# Power_-_Input.net
KiCad netlist of a schematic drawn in Altium Designer
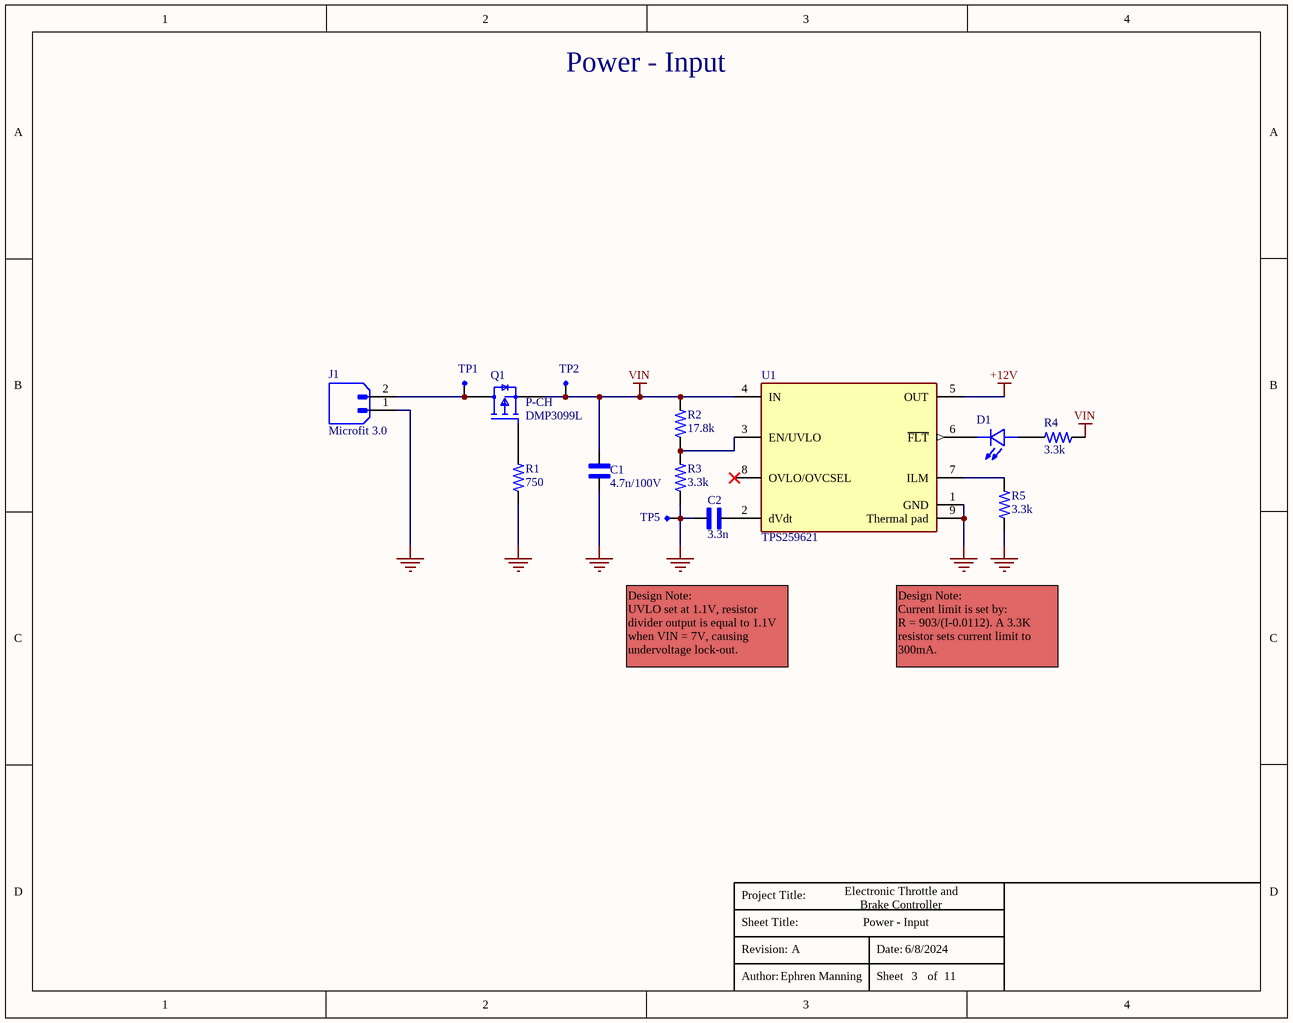
[diagram p0: Power - Input.SchDoc]

(export (version "E")
  (design (tool "Eeschema 10.0.6"))
  (components
    (comp (ref "C1")
      (value "4.7n/100V")
      (footprint "CAP_0402-Footprint-1")
      (description "4.7nF 100V 10% 0402 Ceramic Capacitor")
      (fields (field (name "DIGIKEY PART NUMBER") "490-4765-1-ND"))
      (libsource (lib "SAE @ UIC Formula Electric") (part "CAP_0402-Symbol-1"))
    )
    (comp (ref "C2")
      (value "3.3n")
      (footprint "CAP_0402-Footprint-1")
      (description "3.3nF 25V 0402 Ceramic Capacitor")
      (fields (field (name "DIGIKEY PART NUMBER") "311-3623-1-ND"))
      (libsource (lib "") (part "CAP_0402-Symbol-1_1"))
    )
    (comp (ref "D1")
      (value "150060RS75000")
      (footprint "LED_150060RS75000")
      (description "CLEAR RED LEAD 0603 2V Forward Voltage")
      (fields (field (name "DIGIKEY PART NUMBER") "732-4978-1-ND"))
      (libsource (lib "SAE @ UIC Formula Electric") (part "150060RS75000"))
    )
    (comp (ref "J1")
      (value "Microfit 3.0")
      (footprint "MOLEX_436500216")
      (description "1x2 Gold Microfit")
      (fields (field (name "DIGIKEY PART NUMBER") "WM1922-ND"))
      (libsource (lib "SAE @ UIC Formula Electric") (part "436500216"))
    )
    (comp (ref "Q1")
      (value "DMP3099L")
      (footprint "SOT95P242X110-3N")
      (description "Mosfet P-CH 30V 3.8A Vgs(ON) = -10V SOT23")
      (fields (field (name "DIGIKEY PART NUMBER") "DMP3099L-7DICT-ND"))
      (libsource (lib "SAE @ UIC Formula Electric") (part "DMP3099L-7-Symbol-1"))
    )
    (comp (ref "R1")
      (value "750")
      (footprint "RES_0402-Footprint-1")
      (description "750 1% 1/16W 0402 Thick Film")
      (fields (field (name "DIGIKEY PART NUMBER") "311-750LRCT-ND"))
      (libsource (lib "SAE @ UIC Formula Electric") (part "RES_0402_Symbol"))
    )
    (comp (ref "R2")
      (value "17.8k")
      (footprint "RES_0402-Footprint-1")
      (description "17.8k 1% 1/16W 0402 Thick Film")
      (fields (field (name "DIGIKEY PART NUMBER") "YAG3012CT-ND"))
      (libsource (lib "SAE @ UIC Formula Electric") (part "RES_0402_Symbol"))
    )
    (comp (ref "R3")
      (value "3.3k")
      (footprint "RES_0402-Footprint-1")
      (description "3.3k 1% 1/16W 0402 Thick Film")
      (fields (field (name "DIGIKEY PART NUMBER") "311-3.30KLRCT-ND"))
      (libsource (lib "SAE @ UIC Formula Electric") (part "RES_0402_Symbol"))
    )
    (comp (ref "R4")
      (value "3.3k")
      (footprint "RES_0402-Footprint-1")
      (description "3.3k 1% 1/16W 0402 Thick Film")
      (fields (field (name "DIGIKEY PART NUMBER") "311-3.30KLRCT-ND"))
      (libsource (lib "SAE @ UIC Formula Electric") (part "RES_0402_Symbol"))
    )
    (comp (ref "R5")
      (value "3.3k")
      (footprint "RES_0402-Footprint-1")
      (description "3.3k 1% 1/16W 0402 Thick Film")
      (fields (field (name "DIGIKEY PART NUMBER") "311-3.30KLRCT-ND"))
      (libsource (lib "SAE @ UIC Formula Electric") (part "RES_0402_Symbol"))
    )
    (comp (ref "TP1")
      (value "SMD Testpoint")
      (footprint "SMD Testpoint-Footprint-1")
      (description "Flat 50x50mil Test Point")
      (libsource (lib "SAE @ UIC Formula Electric") (part "SMD Testpoint-Symbol-1"))
    )
    (comp (ref "TP2")
      (value "SMD Testpoint")
      (footprint "SMD Testpoint-Footprint-1")
      (description "Flat 50x50mil Test Point")
      (libsource (lib "SAE @ UIC Formula Electric") (part "SMD Testpoint-Symbol-1"))
    )
    (comp (ref "TP5")
      (value "SMD Testpoint")
      (footprint "SMD Testpoint-Footprint-1")
      (description "Flat 50x50mil Test Point")
      (libsource (lib "SAE @ UIC Formula Electric") (part "SMD Testpoint-Symbol-1"))
    )
    (comp (ref "U1")
      (value "TPS259621")
      (footprint "FP-DDA0008E-IPC_B")
      (description "19V 2A EFUSE")
      (fields (field (name "DIGIKEY PART NUMBER") "296-TPS259621DDATCT-ND"))
      (libsource (lib "SAE @ UIC Formula Electric") (part "TPS2596-Symbol"))
    )
  )
  (nets
    (net (code "1") (name "+12V") (class "Default")
      (node (ref "U1") (pin "5") (pinfunction "OUT_5") (pintype "power_in"))
    )
    (net (code "2") (name "GND") (class "Default")
      (node (ref "C1") (pin "1") (pinfunction "1_1") (pintype "passive"))
      (node (ref "C2") (pin "1") (pinfunction "1_1") (pintype "passive"))
      (node (ref "J1") (pin "1") (pinfunction "1_1") (pintype "passive"))
      (node (ref "R1") (pin "1") (pinfunction "1_1") (pintype "passive"))
      (node (ref "R3") (pin "1") (pinfunction "1_1") (pintype "passive"))
      (node (ref "R5") (pin "1") (pinfunction "1_1") (pintype "passive"))
      (node (ref "TP5") (pin "1") (pinfunction "1_1") (pintype "passive"))
      (node (ref "U1") (pin "1") (pinfunction "GND_1") (pintype "power_in"))
      (node (ref "U1") (pin "9") (pinfunction "Thermal_pad_9") (pintype "power_in"))
    )
    (net (code "3") (name "Net-(D1-PadA)") (class "Default")
      (node (ref "D1") (pin "A") (pinfunction "A_A") (pintype "passive"))
      (node (ref "R4") (pin "2") (pinfunction "2_2") (pintype "passive"))
    )
    (net (code "4") (name "Net-(Q1-Drain)") (class "Default")
      (node (ref "J1") (pin "2") (pinfunction "2_2") (pintype "passive"))
      (node (ref "Q1") (pin "3") (pinfunction "Drain_3") (pintype "passive"))
      (node (ref "TP1") (pin "1") (pinfunction "1_1") (pintype "passive"))
    )
    (net (code "5") (name "Net-(Q1-Gate)") (class "Default")
      (node (ref "Q1") (pin "1") (pinfunction "Gate_1") (pintype "passive"))
      (node (ref "R1") (pin "2") (pinfunction "2_2") (pintype "passive"))
    )
    (net (code "6") (name "Net-(U1-EN{slash}UVLO)") (class "Default")
      (node (ref "R2") (pin "1") (pinfunction "1_1") (pintype "passive"))
      (node (ref "R3") (pin "2") (pinfunction "2_2") (pintype "passive"))
      (node (ref "U1") (pin "3") (pinfunction "EN/UVLO_3") (pintype "passive"))
    )
    (net (code "7") (name "Net-(U1-ILM)") (class "Default")
      (node (ref "R5") (pin "2") (pinfunction "2_2") (pintype "passive"))
      (node (ref "U1") (pin "7") (pinfunction "ILM_7") (pintype "passive"))
    )
    (net (code "8") (name "Net-(U1-dVdt)") (class "Default")
      (node (ref "C2") (pin "2") (pinfunction "2_2") (pintype "passive"))
      (node (ref "U1") (pin "2") (pinfunction "dVdt_2") (pintype "passive"))
    )
    (net (code "9") (name "Net-(U1-~{FLT})") (class "Default")
      (node (ref "D1") (pin "C") (pinfunction "C_C") (pintype "passive"))
      (node (ref "U1") (pin "6") (pinfunction "~{FLT}_6") (pintype "output"))
    )
    (net (code "10") (name "VIN") (class "Default")
      (node (ref "C1") (pin "2") (pinfunction "2_2") (pintype "passive"))
      (node (ref "Q1") (pin "2") (pinfunction "Source_2") (pintype "passive"))
      (node (ref "R2") (pin "2") (pinfunction "2_2") (pintype "passive"))
      (node (ref "R4") (pin "1") (pinfunction "1_1") (pintype "passive"))
      (node (ref "TP2") (pin "1") (pinfunction "1_1") (pintype "passive"))
      (node (ref "U1") (pin "4") (pinfunction "IN_4") (pintype "power_in"))
    )
    (net (code "11") (name "unconnected-(U1-OVLO{slash}OVCSEL-Pad8)") (class "Default")
      (node (ref "U1") (pin "8") (pinfunction "OVLO/OVCSEL_8") (pintype "passive+no_connect"))
    )
  )
)
